# TeslaBMS_Shield_2.net
KiCad netlist of a schematic drawn in EAGLE
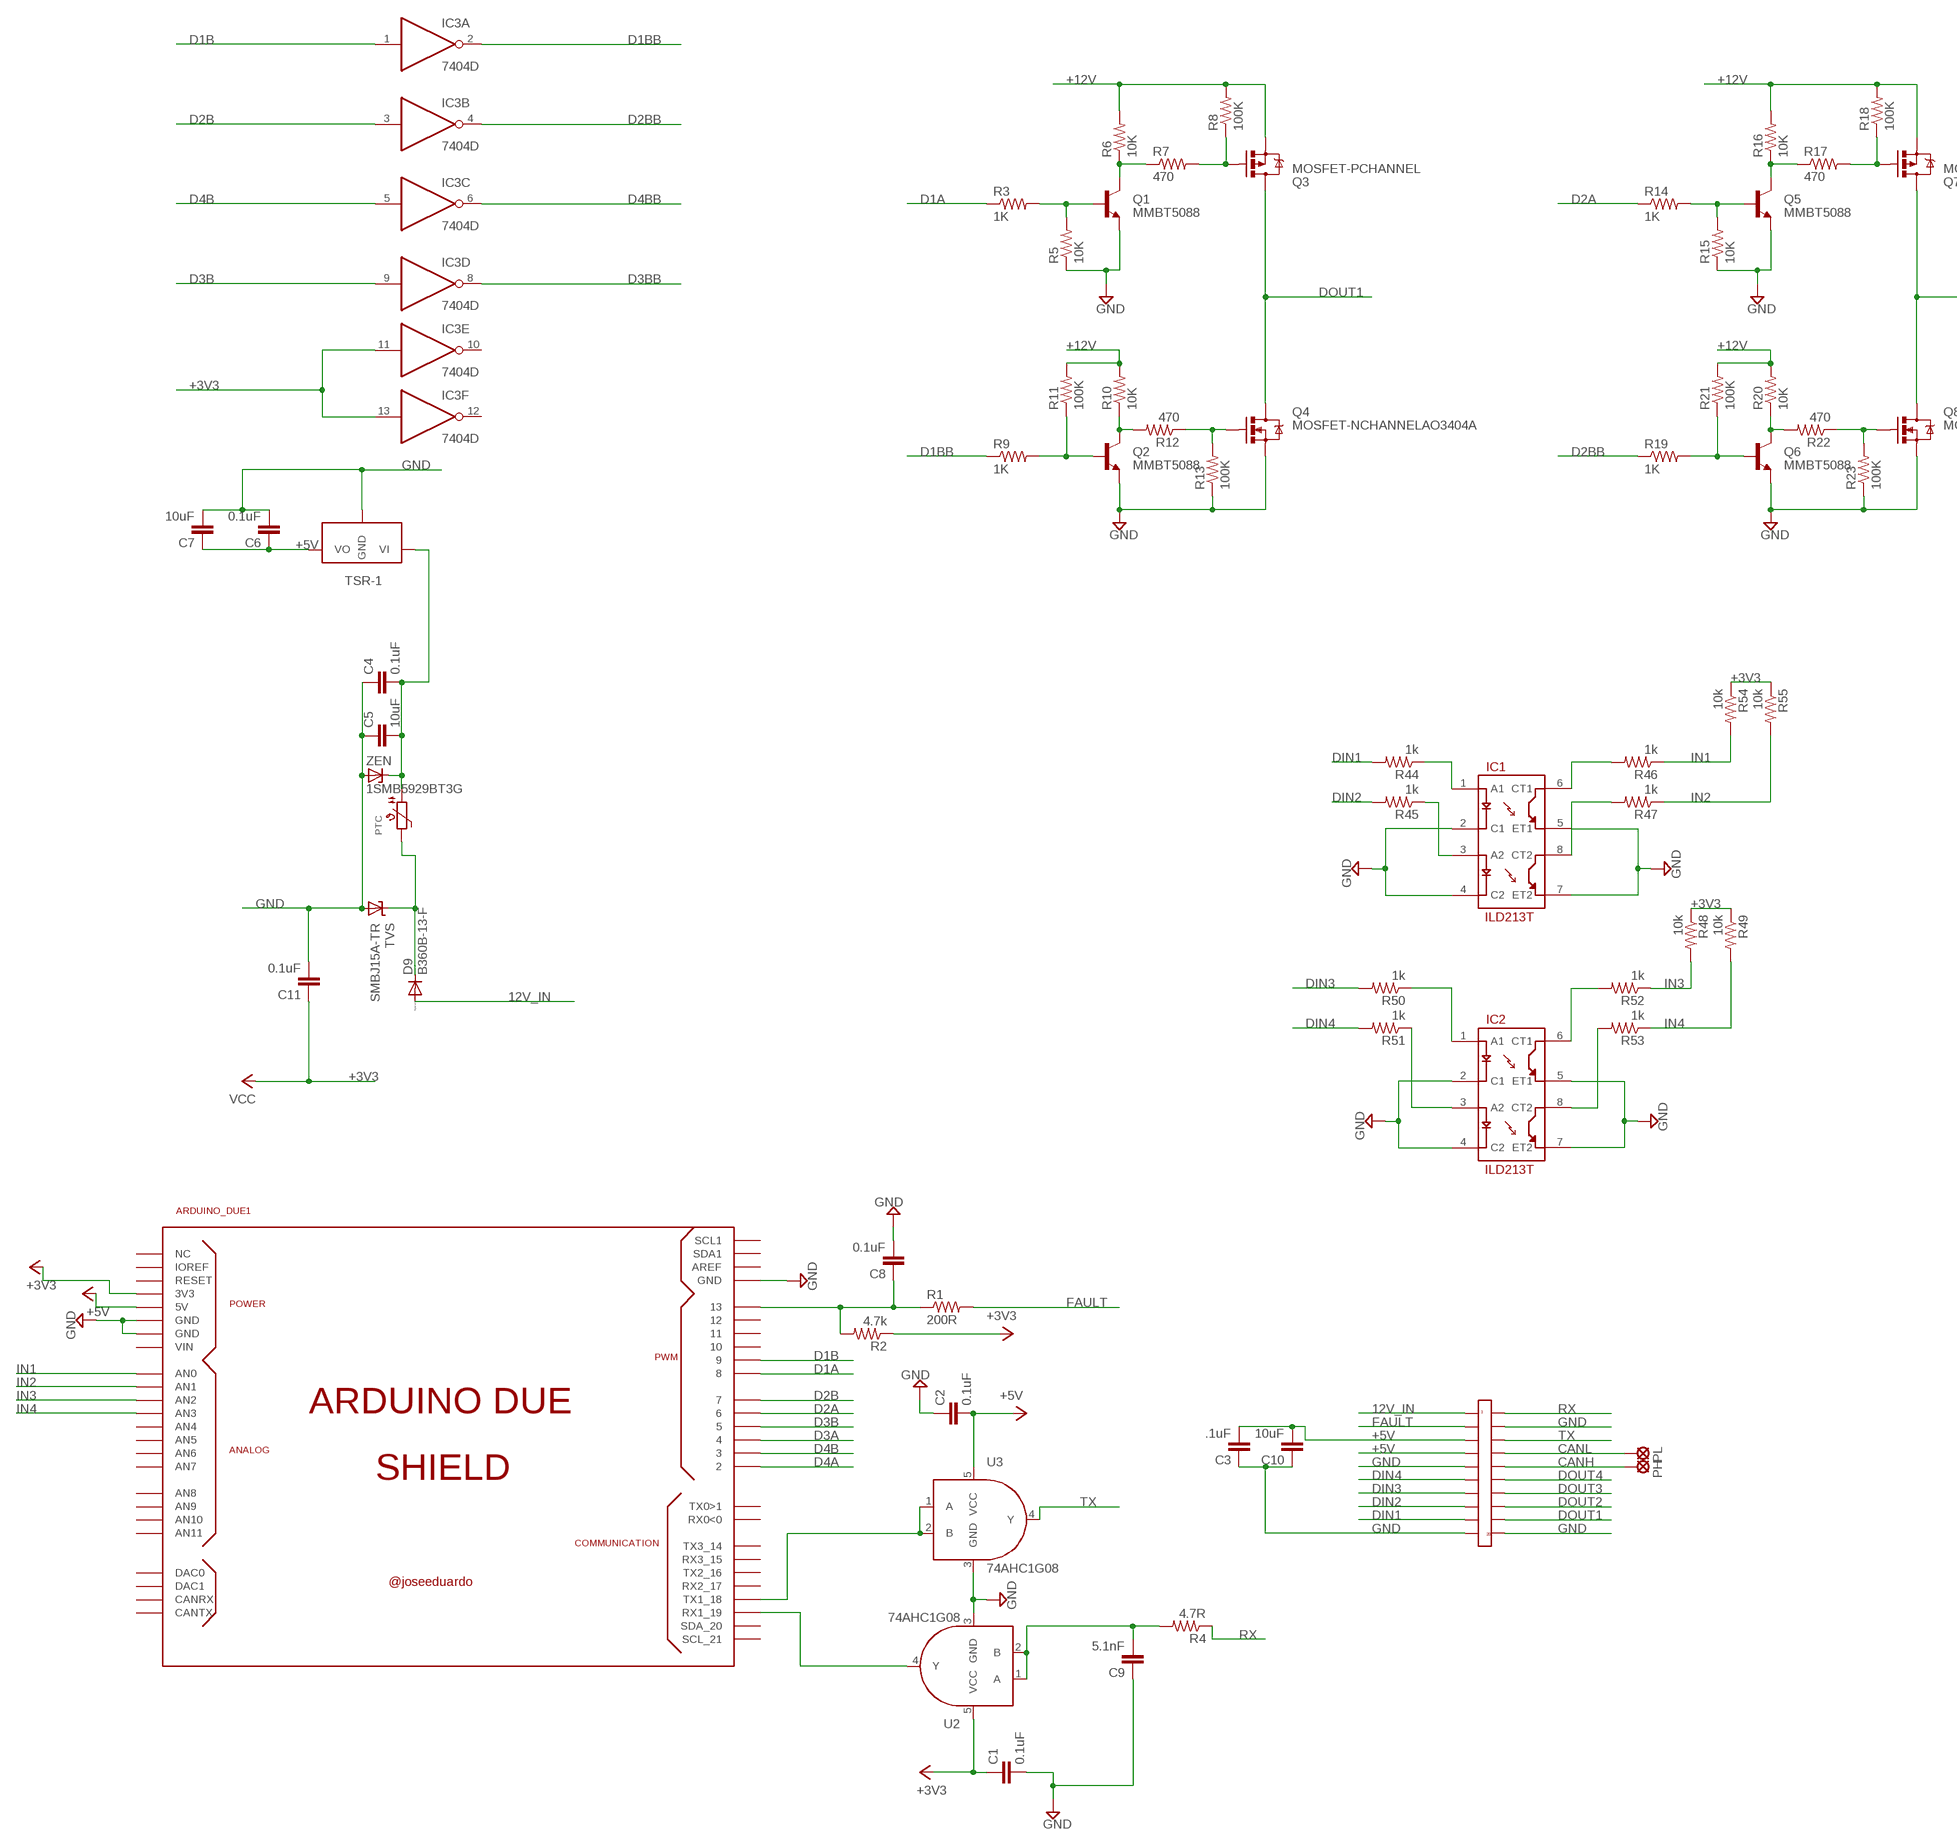
[diagram p0: schematic, sheet 1, part 1 of 2]
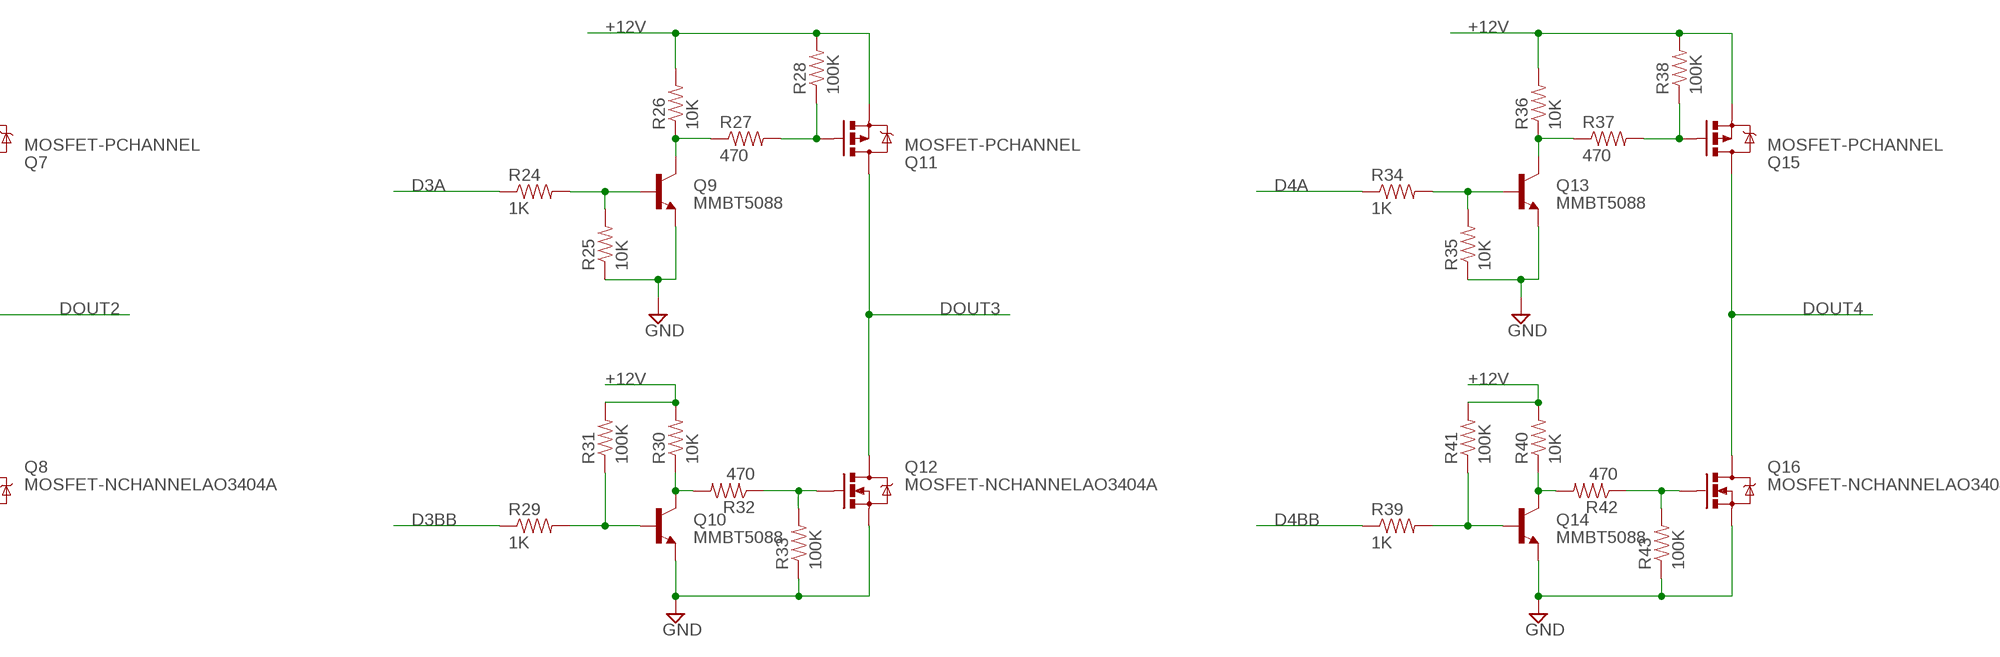
[diagram p1: schematic, sheet 1, part 2 of 2]

(export (version "E")
  (design (tool "Eeschema 10.0.6"))
  (components
    (comp (ref "ARDUINO_DUE1")
      (value "ARDUINO_DUE_SHIELD")
      (footprint "eagle-import:ARDUINO_DUE_SHIELD")
      (libsource (lib "eagle-import") (part "ARDUINO_DUE_SHIELD"))
    )
    (comp (ref "C1")
      (value "0.1uF")
      (footprint "eagle-import:0603-CAP")
      (libsource (lib "eagle-import") (part "CAP0603-CAP"))
    )
    (comp (ref "C2")
      (value "0.1uF")
      (footprint "eagle-import:0603-CAP")
      (libsource (lib "eagle-import") (part "CAP0603-CAP"))
    )
    (comp (ref "C3")
      (value ".1uF")
      (footprint "eagle-import:0603-CAP")
      (libsource (lib "eagle-import") (part "CAP0603-CAP"))
    )
    (comp (ref "C4")
      (value "0.1uF")
      (footprint "eagle-import:0805")
      (libsource (lib "eagle-import") (part "CAP0805"))
    )
    (comp (ref "C5")
      (value "10uF")
      (footprint "eagle-import:0805")
      (libsource (lib "eagle-import") (part "CAP0805"))
    )
    (comp (ref "C6")
      (value "0.1uF")
      (footprint "eagle-import:0805")
      (libsource (lib "eagle-import") (part "CAP0805"))
    )
    (comp (ref "C7")
      (value "10uF")
      (footprint "eagle-import:0805")
      (libsource (lib "eagle-import") (part "CAP0805"))
    )
    (comp (ref "C8")
      (value "0.1uF")
      (footprint "eagle-import:0603-CAP")
      (libsource (lib "eagle-import") (part "CAP0603-CAP"))
    )
    (comp (ref "C9")
      (value "5.1nF")
      (footprint "eagle-import:0603-CAP")
      (libsource (lib "eagle-import") (part "CAP0603-CAP"))
    )
    (comp (ref "C10")
      (value "10uF")
      (footprint "eagle-import:0603-CAP")
      (libsource (lib "eagle-import") (part "CAP0603-CAP"))
    )
    (comp (ref "C11")
      (value "0.1uF")
      (footprint "eagle-import:0805")
      (libsource (lib "eagle-import") (part "CAP0805"))
    )
    (comp (ref "D9")
      (value "B360B-13-F")
      (footprint "eagle-import:SMB")
      (libsource (lib "eagle-import") (part "DIODE-SMB"))
    )
    (comp (ref "IC1")
      (value "ILD213T")
      (footprint "eagle-import:SO08")
      (libsource (lib "eagle-import") (part "ILD213T"))
    )
    (comp (ref "IC2")
      (value "ILD213T")
      (footprint "eagle-import:SO08")
      (libsource (lib "eagle-import") (part "ILD213T"))
    )
    (comp (ref "IC3")
      (value "7404D")
      (footprint "eagle-import:SO14")
      (libsource (lib "eagle-import") (part "7404D"))
    )
    (comp (ref "PH")
      (value "SE11")
      (footprint "eagle-import:SE11")
      (libsource (lib "eagle-import") (part "SE11"))
    )
    (comp (ref "PL")
      (value "SE11")
      (footprint "eagle-import:SE11")
      (libsource (lib "eagle-import") (part "SE11"))
    )
    (comp (ref "PTC")
      (value "PTC1812")
      (footprint "eagle-import:PTC1812")
      (libsource (lib "eagle-import") (part "PTC1812"))
    )
    (comp (ref "Q1")
      (value "MMBT5088")
      (footprint "eagle-import:SOT23-3")
      (libsource (lib "eagle-import") (part "TRANSISTOR_NPNMMBT5088"))
    )
    (comp (ref "Q2")
      (value "MMBT5088")
      (footprint "eagle-import:SOT23-3")
      (libsource (lib "eagle-import") (part "TRANSISTOR_NPNMMBT5088"))
    )
    (comp (ref "Q3")
      (value "MOSFET-PCHANNEL")
      (footprint "eagle-import:SOT23-3")
      (libsource (lib "eagle-import") (part "MOSFET-PCHANNEL"))
    )
    (comp (ref "Q4")
      (value "MOSFET-NCHANNELAO3404A")
      (footprint "eagle-import:SOT23-3")
      (libsource (lib "eagle-import") (part "MOSFET-NCHANNELAO3404A"))
    )
    (comp (ref "Q5")
      (value "MMBT5088")
      (footprint "eagle-import:SOT23-3")
      (libsource (lib "eagle-import") (part "TRANSISTOR_NPNMMBT5088"))
    )
    (comp (ref "Q6")
      (value "MMBT5088")
      (footprint "eagle-import:SOT23-3")
      (libsource (lib "eagle-import") (part "TRANSISTOR_NPNMMBT5088"))
    )
    (comp (ref "Q7")
      (value "MOSFET-PCHANNEL")
      (footprint "eagle-import:SOT23-3")
      (libsource (lib "eagle-import") (part "MOSFET-PCHANNEL"))
    )
    (comp (ref "Q8")
      (value "MOSFET-NCHANNELAO3404A")
      (footprint "eagle-import:SOT23-3")
      (libsource (lib "eagle-import") (part "MOSFET-NCHANNELAO3404A"))
    )
    (comp (ref "Q9")
      (value "MMBT5088")
      (footprint "eagle-import:SOT23-3")
      (libsource (lib "eagle-import") (part "TRANSISTOR_NPNMMBT5088"))
    )
    (comp (ref "Q10")
      (value "MMBT5088")
      (footprint "eagle-import:SOT23-3")
      (libsource (lib "eagle-import") (part "TRANSISTOR_NPNMMBT5088"))
    )
    (comp (ref "Q11")
      (value "MOSFET-PCHANNEL")
      (footprint "eagle-import:SOT23-3")
      (libsource (lib "eagle-import") (part "MOSFET-PCHANNEL"))
    )
    (comp (ref "Q12")
      (value "MOSFET-NCHANNELAO3404A")
      (footprint "eagle-import:SOT23-3")
      (libsource (lib "eagle-import") (part "MOSFET-NCHANNELAO3404A"))
    )
    (comp (ref "Q13")
      (value "MMBT5088")
      (footprint "eagle-import:SOT23-3")
      (libsource (lib "eagle-import") (part "TRANSISTOR_NPNMMBT5088"))
    )
    (comp (ref "Q14")
      (value "MMBT5088")
      (footprint "eagle-import:SOT23-3")
      (libsource (lib "eagle-import") (part "TRANSISTOR_NPNMMBT5088"))
    )
    (comp (ref "Q15")
      (value "MOSFET-PCHANNEL")
      (footprint "eagle-import:SOT23-3")
      (libsource (lib "eagle-import") (part "MOSFET-PCHANNEL"))
    )
    (comp (ref "Q16")
      (value "MOSFET-NCHANNELAO3404A")
      (footprint "eagle-import:SOT23-3")
      (libsource (lib "eagle-import") (part "MOSFET-NCHANNELAO3404A"))
    )
    (comp (ref "R1")
      (value "200R")
      (footprint "eagle-import:0603-RES")
      (libsource (lib "eagle-import") (part "RESISTOR0603-RES"))
    )
    (comp (ref "R2")
      (value "4.7k")
      (footprint "eagle-import:0603-RES")
      (libsource (lib "eagle-import") (part "RESISTOR0603-RES"))
    )
    (comp (ref "R3")
      (value "1K")
      (footprint "eagle-import:0402-RES")
      (libsource (lib "eagle-import") (part "RESISTOR0402"))
    )
    (comp (ref "R4")
      (value "4.7R")
      (footprint "eagle-import:0603-RES")
      (libsource (lib "eagle-import") (part "RESISTOR0603-RES"))
    )
    (comp (ref "R5")
      (value "10K")
      (footprint "eagle-import:0402-RES")
      (libsource (lib "eagle-import") (part "RESISTOR0402"))
    )
    (comp (ref "R6")
      (value "10K")
      (footprint "eagle-import:0402-RES")
      (libsource (lib "eagle-import") (part "RESISTOR0402"))
    )
    (comp (ref "R7")
      (value "470")
      (footprint "eagle-import:0402-RES")
      (libsource (lib "eagle-import") (part "RESISTOR0402"))
    )
    (comp (ref "R8")
      (value "100K")
      (footprint "eagle-import:0402-RES")
      (libsource (lib "eagle-import") (part "RESISTOR0402"))
    )
    (comp (ref "R9")
      (value "1K")
      (footprint "eagle-import:0402-RES")
      (libsource (lib "eagle-import") (part "RESISTOR0402"))
    )
    (comp (ref "R10")
      (value "10K")
      (footprint "eagle-import:0402-RES")
      (libsource (lib "eagle-import") (part "RESISTOR0402"))
    )
    (comp (ref "R11")
      (value "100K")
      (footprint "eagle-import:0402-RES")
      (libsource (lib "eagle-import") (part "RESISTOR0402"))
    )
    (comp (ref "R12")
      (value "470")
      (footprint "eagle-import:0402-RES")
      (libsource (lib "eagle-import") (part "RESISTOR0402"))
    )
    (comp (ref "R13")
      (value "100K")
      (footprint "eagle-import:0402-RES")
      (libsource (lib "eagle-import") (part "RESISTOR0402"))
    )
    (comp (ref "R14")
      (value "1K")
      (footprint "eagle-import:0402-RES")
      (libsource (lib "eagle-import") (part "RESISTOR0402"))
    )
    (comp (ref "R15")
      (value "10K")
      (footprint "eagle-import:0402-RES")
      (libsource (lib "eagle-import") (part "RESISTOR0402"))
    )
    (comp (ref "R16")
      (value "10K")
      (footprint "eagle-import:0402-RES")
      (libsource (lib "eagle-import") (part "RESISTOR0402"))
    )
    (comp (ref "R17")
      (value "470")
      (footprint "eagle-import:0402-RES")
      (libsource (lib "eagle-import") (part "RESISTOR0402"))
    )
    (comp (ref "R18")
      (value "100K")
      (footprint "eagle-import:0402-RES")
      (libsource (lib "eagle-import") (part "RESISTOR0402"))
    )
    (comp (ref "R19")
      (value "1K")
      (footprint "eagle-import:0402-RES")
      (libsource (lib "eagle-import") (part "RESISTOR0402"))
    )
    (comp (ref "R20")
      (value "10K")
      (footprint "eagle-import:0402-RES")
      (libsource (lib "eagle-import") (part "RESISTOR0402"))
    )
    (comp (ref "R21")
      (value "100K")
      (footprint "eagle-import:0402-RES")
      (libsource (lib "eagle-import") (part "RESISTOR0402"))
    )
    (comp (ref "R22")
      (value "470")
      (footprint "eagle-import:0402-RES")
      (libsource (lib "eagle-import") (part "RESISTOR0402"))
    )
    (comp (ref "R23")
      (value "100K")
      (footprint "eagle-import:0402-RES")
      (libsource (lib "eagle-import") (part "RESISTOR0402"))
    )
    (comp (ref "R24")
      (value "1K")
      (footprint "eagle-import:0402-RES")
      (libsource (lib "eagle-import") (part "RESISTOR0402"))
    )
    (comp (ref "R25")
      (value "10K")
      (footprint "eagle-import:0402-RES")
      (libsource (lib "eagle-import") (part "RESISTOR0402"))
    )
    (comp (ref "R26")
      (value "10K")
      (footprint "eagle-import:0402-RES")
      (libsource (lib "eagle-import") (part "RESISTOR0402"))
    )
    (comp (ref "R27")
      (value "470")
      (footprint "eagle-import:0402-RES")
      (libsource (lib "eagle-import") (part "RESISTOR0402"))
    )
    (comp (ref "R28")
      (value "100K")
      (footprint "eagle-import:0402-RES")
      (libsource (lib "eagle-import") (part "RESISTOR0402"))
    )
    (comp (ref "R29")
      (value "1K")
      (footprint "eagle-import:0402-RES")
      (libsource (lib "eagle-import") (part "RESISTOR0402"))
    )
    (comp (ref "R30")
      (value "10K")
      (footprint "eagle-import:0402-RES")
      (libsource (lib "eagle-import") (part "RESISTOR0402"))
    )
    (comp (ref "R31")
      (value "100K")
      (footprint "eagle-import:0402-RES")
      (libsource (lib "eagle-import") (part "RESISTOR0402"))
    )
    (comp (ref "R32")
      (value "470")
      (footprint "eagle-import:0402-RES")
      (libsource (lib "eagle-import") (part "RESISTOR0402"))
    )
    (comp (ref "R33")
      (value "100K")
      (footprint "eagle-import:0402-RES")
      (libsource (lib "eagle-import") (part "RESISTOR0402"))
    )
    (comp (ref "R34")
      (value "1K")
      (footprint "eagle-import:0402-RES")
      (libsource (lib "eagle-import") (part "RESISTOR0402"))
    )
    (comp (ref "R35")
      (value "10K")
      (footprint "eagle-import:0402-RES")
      (libsource (lib "eagle-import") (part "RESISTOR0402"))
    )
    (comp (ref "R36")
      (value "10K")
      (footprint "eagle-import:0402-RES")
      (libsource (lib "eagle-import") (part "RESISTOR0402"))
    )
    (comp (ref "R37")
      (value "470")
      (footprint "eagle-import:0402-RES")
      (libsource (lib "eagle-import") (part "RESISTOR0402"))
    )
    (comp (ref "R38")
      (value "100K")
      (footprint "eagle-import:0402-RES")
      (libsource (lib "eagle-import") (part "RESISTOR0402"))
    )
    (comp (ref "R39")
      (value "1K")
      (footprint "eagle-import:0402-RES")
      (libsource (lib "eagle-import") (part "RESISTOR0402"))
    )
    (comp (ref "R40")
      (value "10K")
      (footprint "eagle-import:0402-RES")
      (libsource (lib "eagle-import") (part "RESISTOR0402"))
    )
    (comp (ref "R41")
      (value "100K")
      (footprint "eagle-import:0402-RES")
      (libsource (lib "eagle-import") (part "RESISTOR0402"))
    )
    (comp (ref "R42")
      (value "470")
      (footprint "eagle-import:0402-RES")
      (libsource (lib "eagle-import") (part "RESISTOR0402"))
    )
    (comp (ref "R43")
      (value "100K")
      (footprint "eagle-import:0402-RES")
      (libsource (lib "eagle-import") (part "RESISTOR0402"))
    )
    (comp (ref "R44")
      (value "1k")
      (footprint "eagle-import:0603-RES")
      (libsource (lib "eagle-import") (part "RESISTOR0603-RES"))
    )
    (comp (ref "R45")
      (value "1k")
      (footprint "eagle-import:0603-RES")
      (libsource (lib "eagle-import") (part "RESISTOR0603-RES"))
    )
    (comp (ref "R46")
      (value "1k")
      (footprint "eagle-import:0603-RES")
      (libsource (lib "eagle-import") (part "RESISTOR0603-RES"))
    )
    (comp (ref "R47")
      (value "1k")
      (footprint "eagle-import:0603-RES")
      (libsource (lib "eagle-import") (part "RESISTOR0603-RES"))
    )
    (comp (ref "R48")
      (value "10k")
      (footprint "eagle-import:0603-RES")
      (libsource (lib "eagle-import") (part "RESISTOR0603-RES"))
    )
    (comp (ref "R49")
      (value "10k")
      (footprint "eagle-import:0603-RES")
      (libsource (lib "eagle-import") (part "RESISTOR0603-RES"))
    )
    (comp (ref "R50")
      (value "1k")
      (footprint "eagle-import:0603-RES")
      (libsource (lib "eagle-import") (part "RESISTOR0603-RES"))
    )
    (comp (ref "R51")
      (value "1k")
      (footprint "eagle-import:0603-RES")
      (libsource (lib "eagle-import") (part "RESISTOR0603-RES"))
    )
    (comp (ref "R52")
      (value "1k")
      (footprint "eagle-import:0603-RES")
      (libsource (lib "eagle-import") (part "RESISTOR0603-RES"))
    )
    (comp (ref "R53")
      (value "1k")
      (footprint "eagle-import:0603-RES")
      (libsource (lib "eagle-import") (part "RESISTOR0603-RES"))
    )
    (comp (ref "R54")
      (value "10k")
      (footprint "eagle-import:0603-RES")
      (libsource (lib "eagle-import") (part "RESISTOR0603-RES"))
    )
    (comp (ref "R55")
      (value "10k")
      (footprint "eagle-import:0603-RES")
      (libsource (lib "eagle-import") (part "RESISTOR0603-RES"))
    )
    (comp (ref "TVS")
      (value "SMBJ15A-TR")
      (footprint "eagle-import:SMBJ")
      (libsource (lib "eagle-import") (part "SUPPRESSOR-SMBJ"))
    )
    (comp (ref "U$2")
      (value "VAL-U-LOK-20PIN")
      (footprint "eagle-import:VALULOK-20")
      (libsource (lib "eagle-import") (part "VAL-U-LOK-20PIN"))
    )
    (comp (ref "U2")
      (value "74AHC1G08")
      (footprint "eagle-import:SOT353")
      (libsource (lib "eagle-import") (part "74AHC1G08"))
    )
    (comp (ref "U3")
      (value "74AHC1G08")
      (footprint "eagle-import:SOT353")
      (libsource (lib "eagle-import") (part "74AHC1G08"))
    )
    (comp (ref "U9")
      (value "TSR-1")
      (footprint "eagle-import:TSR-1")
      (libsource (lib "eagle-import") (part "TSR-1"))
    )
    (comp (ref "ZEN")
      (value "1SMB5929BT3G")
      (footprint "eagle-import:SMB")
      (libsource (lib "eagle-import") (part "ZENER-DIODESMB"))
    )
  )
  (nets
    (net (code "1") (name "+3V3") (class "Default")
      (node (ref "ARDUINO_DUE1") (pin "3V3") (pinfunction "3V3_3V3") (pintype "bidirectional"))
      (node (ref "C1") (pin "1") (pinfunction "1_1") (pintype "passive"))
      (node (ref "C11") (pin "1") (pinfunction "1_1") (pintype "passive"))
      (node (ref "IC3") (pin "11") (pinfunction "I_11") (pintype "input"))
      (node (ref "IC3") (pin "13") (pinfunction "I_13") (pintype "input"))
      (node (ref "R2") (pin "1") (pinfunction "1_1") (pintype "passive"))
      (node (ref "R48") (pin "1") (pinfunction "1_1") (pintype "passive"))
      (node (ref "R49") (pin "1") (pinfunction "1_1") (pintype "passive"))
      (node (ref "R54") (pin "1") (pinfunction "1_1") (pintype "passive"))
      (node (ref "R55") (pin "1") (pinfunction "1_1") (pintype "passive"))
      (node (ref "U2") (pin "5") (pinfunction "VCC_5") (pintype "bidirectional"))
    )
    (net (code "2") (name "+5V") (class "Default")
      (node (ref "ARDUINO_DUE1") (pin "5V0") (pinfunction "5V_5V0") (pintype "bidirectional"))
      (node (ref "C10") (pin "2") (pinfunction "2_2") (pintype "passive"))
      (node (ref "C2") (pin "2") (pinfunction "2_2") (pintype "passive"))
      (node (ref "C3") (pin "2") (pinfunction "2_2") (pintype "passive"))
      (node (ref "C6") (pin "1") (pinfunction "1_1") (pintype "passive"))
      (node (ref "C7") (pin "1") (pinfunction "1_1") (pintype "passive"))
      (node (ref "U$2") (pin "P$3") (pinfunction "P$3_P$3") (pintype "bidirectional"))
      (node (ref "U$2") (pin "P$4") (pinfunction "P$4_P$4") (pintype "bidirectional"))
      (node (ref "U3") (pin "5") (pinfunction "VCC_5") (pintype "bidirectional"))
      (node (ref "U9") (pin "P$3") (pinfunction "VO_P$3") (pintype "bidirectional"))
    )
    (net (code "3") (name "/+12V") (class "Default")
      (node (ref "C4") (pin "2") (pinfunction "2_2") (pintype "passive"))
      (node (ref "C5") (pin "2") (pinfunction "2_2") (pintype "passive"))
      (node (ref "PTC") (pin "P$1") (pinfunction "1_P$1") (pintype "passive"))
      (node (ref "Q11") (pin "2") (pinfunction "S_2") (pintype "passive"))
      (node (ref "Q15") (pin "2") (pinfunction "S_2") (pintype "passive"))
      (node (ref "Q3") (pin "2") (pinfunction "S_2") (pintype "passive"))
      (node (ref "Q7") (pin "2") (pinfunction "S_2") (pintype "passive"))
      (node (ref "R10") (pin "2") (pinfunction "2_2") (pintype "passive"))
      (node (ref "R11") (pin "2") (pinfunction "2_2") (pintype "passive"))
      (node (ref "R16") (pin "2") (pinfunction "2_2") (pintype "passive"))
      (node (ref "R18") (pin "2") (pinfunction "2_2") (pintype "passive"))
      (node (ref "R20") (pin "2") (pinfunction "2_2") (pintype "passive"))
      (node (ref "R21") (pin "2") (pinfunction "2_2") (pintype "passive"))
      (node (ref "R26") (pin "2") (pinfunction "2_2") (pintype "passive"))
      (node (ref "R28") (pin "2") (pinfunction "2_2") (pintype "passive"))
      (node (ref "R30") (pin "2") (pinfunction "2_2") (pintype "passive"))
      (node (ref "R31") (pin "2") (pinfunction "2_2") (pintype "passive"))
      (node (ref "R36") (pin "2") (pinfunction "2_2") (pintype "passive"))
      (node (ref "R38") (pin "2") (pinfunction "2_2") (pintype "passive"))
      (node (ref "R40") (pin "2") (pinfunction "2_2") (pintype "passive"))
      (node (ref "R41") (pin "2") (pinfunction "2_2") (pintype "passive"))
      (node (ref "R6") (pin "2") (pinfunction "2_2") (pintype "passive"))
      (node (ref "R8") (pin "2") (pinfunction "2_2") (pintype "passive"))
      (node (ref "U9") (pin "P$1") (pinfunction "VI_P$1") (pintype "bidirectional"))
      (node (ref "ZEN") (pin "C") (pinfunction "C_C") (pintype "passive"))
    )
    (net (code "4") (name "/12V_IN") (class "Default")
      (node (ref "D9") (pin "A") (pinfunction "A_A") (pintype "passive"))
      (node (ref "U$2") (pin "P$1") (pinfunction "P$1_P$1") (pintype "bidirectional"))
    )
    (net (code "5") (name "/CANH") (class "Default")
      (node (ref "PH") (pin "MP") (pinfunction "MP_MP") (pintype "passive"))
      (node (ref "U$2") (pin "P$15") (pinfunction "P$15_P$15") (pintype "bidirectional"))
    )
    (net (code "6") (name "/CANL") (class "Default")
      (node (ref "PL") (pin "MP") (pinfunction "MP_MP") (pintype "passive"))
      (node (ref "U$2") (pin "P$14") (pinfunction "P$14_P$14") (pintype "bidirectional"))
    )
    (net (code "7") (name "/D1A") (class "Default")
      (node (ref "ARDUINO_DUE1") (pin "8") (pinfunction "8_8") (pintype "bidirectional"))
      (node (ref "R3") (pin "1") (pinfunction "1_1") (pintype "passive"))
    )
    (net (code "8") (name "/D1B") (class "Default")
      (node (ref "ARDUINO_DUE1") (pin "9") (pinfunction "9_9") (pintype "bidirectional"))
      (node (ref "IC3") (pin "1") (pinfunction "I_1") (pintype "input"))
    )
    (net (code "9") (name "/D1BB") (class "Default")
      (node (ref "IC3") (pin "2") (pinfunction "O_2") (pintype "output"))
      (node (ref "R9") (pin "1") (pinfunction "1_1") (pintype "passive"))
    )
    (net (code "10") (name "/D2A") (class "Default")
      (node (ref "ARDUINO_DUE1") (pin "6") (pinfunction "6_6") (pintype "bidirectional"))
      (node (ref "R14") (pin "1") (pinfunction "1_1") (pintype "passive"))
    )
    (net (code "11") (name "/D2B") (class "Default")
      (node (ref "ARDUINO_DUE1") (pin "7") (pinfunction "7_7") (pintype "bidirectional"))
      (node (ref "IC3") (pin "3") (pinfunction "I_3") (pintype "input"))
    )
    (net (code "12") (name "/D2BB") (class "Default")
      (node (ref "IC3") (pin "4") (pinfunction "O_4") (pintype "output"))
      (node (ref "R19") (pin "1") (pinfunction "1_1") (pintype "passive"))
    )
    (net (code "13") (name "/D3A") (class "Default")
      (node (ref "ARDUINO_DUE1") (pin "4") (pinfunction "4_4") (pintype "bidirectional"))
      (node (ref "R24") (pin "1") (pinfunction "1_1") (pintype "passive"))
    )
    (net (code "14") (name "/D3B") (class "Default")
      (node (ref "ARDUINO_DUE1") (pin "5") (pinfunction "5_5") (pintype "bidirectional"))
      (node (ref "IC3") (pin "9") (pinfunction "I_9") (pintype "input"))
    )
    (net (code "15") (name "/D3BB") (class "Default")
      (node (ref "IC3") (pin "8") (pinfunction "O_8") (pintype "output"))
      (node (ref "R29") (pin "1") (pinfunction "1_1") (pintype "passive"))
    )
    (net (code "16") (name "/D4A") (class "Default")
      (node (ref "ARDUINO_DUE1") (pin "2") (pinfunction "2_2") (pintype "bidirectional"))
      (node (ref "R34") (pin "1") (pinfunction "1_1") (pintype "passive"))
    )
    (net (code "17") (name "/D4B") (class "Default")
      (node (ref "ARDUINO_DUE1") (pin "3") (pinfunction "3_3") (pintype "bidirectional"))
      (node (ref "IC3") (pin "5") (pinfunction "I_5") (pintype "input"))
    )
    (net (code "18") (name "/D4BB") (class "Default")
      (node (ref "IC3") (pin "6") (pinfunction "O_6") (pintype "output"))
      (node (ref "R39") (pin "1") (pinfunction "1_1") (pintype "passive"))
    )
    (net (code "19") (name "/DIN1") (class "Default")
      (node (ref "R44") (pin "2") (pinfunction "2_2") (pintype "passive"))
      (node (ref "U$2") (pin "P$9") (pinfunction "P$9_P$9") (pintype "bidirectional"))
    )
    (net (code "20") (name "/DIN2") (class "Default")
      (node (ref "R45") (pin "2") (pinfunction "2_2") (pintype "passive"))
      (node (ref "U$2") (pin "P$8") (pinfunction "P$8_P$8") (pintype "bidirectional"))
    )
    (net (code "21") (name "/DIN3") (class "Default")
      (node (ref "R50") (pin "2") (pinfunction "2_2") (pintype "passive"))
      (node (ref "U$2") (pin "P$7") (pinfunction "P$7_P$7") (pintype "bidirectional"))
    )
    (net (code "22") (name "/DIN4") (class "Default")
      (node (ref "R51") (pin "2") (pinfunction "2_2") (pintype "passive"))
      (node (ref "U$2") (pin "P$6") (pinfunction "P$6_P$6") (pintype "bidirectional"))
    )
    (net (code "23") (name "/DOUT1") (class "Default")
      (node (ref "Q3") (pin "3") (pinfunction "D_3") (pintype "passive"))
      (node (ref "Q4") (pin "3") (pinfunction "D_3") (pintype "passive"))
      (node (ref "U$2") (pin "P$19") (pinfunction "P$19_P$19") (pintype "bidirectional"))
    )
    (net (code "24") (name "/DOUT2") (class "Default")
      (node (ref "Q7") (pin "3") (pinfunction "D_3") (pintype "passive"))
      (node (ref "Q8") (pin "3") (pinfunction "D_3") (pintype "passive"))
      (node (ref "U$2") (pin "P$18") (pinfunction "P$18_P$18") (pintype "bidirectional"))
    )
    (net (code "25") (name "/DOUT3") (class "Default")
      (node (ref "Q11") (pin "3") (pinfunction "D_3") (pintype "passive"))
      (node (ref "Q12") (pin "3") (pinfunction "D_3") (pintype "passive"))
      (node (ref "U$2") (pin "P$17") (pinfunction "P$17_P$17") (pintype "bidirectional"))
    )
    (net (code "26") (name "/DOUT4") (class "Default")
      (node (ref "Q15") (pin "3") (pinfunction "D_3") (pintype "passive"))
      (node (ref "Q16") (pin "3") (pinfunction "D_3") (pintype "passive"))
      (node (ref "U$2") (pin "P$16") (pinfunction "P$16_P$16") (pintype "bidirectional"))
    )
    (net (code "27") (name "/FAULT") (class "Default")
      (node (ref "R1") (pin "2") (pinfunction "2_2") (pintype "passive"))
      (node (ref "U$2") (pin "P$2") (pinfunction "P$2_P$2") (pintype "bidirectional"))
    )
    (net (code "28") (name "/IN1") (class "Default")
      (node (ref "ARDUINO_DUE1") (pin "A0") (pinfunction "AN0_A0") (pintype "bidirectional"))
      (node (ref "R46") (pin "1") (pinfunction "1_1") (pintype "passive"))
      (node (ref "R54") (pin "2") (pinfunction "2_2") (pintype "passive"))
    )
    (net (code "29") (name "/IN2") (class "Default")
      (node (ref "ARDUINO_DUE1") (pin "A1") (pinfunction "AN1_A1") (pintype "bidirectional"))
      (node (ref "R47") (pin "1") (pinfunction "1_1") (pintype "passive"))
      (node (ref "R55") (pin "2") (pinfunction "2_2") (pintype "passive"))
    )
    (net (code "30") (name "/IN3") (class "Default")
      (node (ref "ARDUINO_DUE1") (pin "A2") (pinfunction "AN2_A2") (pintype "bidirectional"))
      (node (ref "R48") (pin "2") (pinfunction "2_2") (pintype "passive"))
      (node (ref "R52") (pin "1") (pinfunction "1_1") (pintype "passive"))
    )
    (net (code "31") (name "/IN4") (class "Default")
      (node (ref "ARDUINO_DUE1") (pin "A3") (pinfunction "AN3_A3") (pintype "bidirectional"))
      (node (ref "R49") (pin "2") (pinfunction "2_2") (pintype "passive"))
      (node (ref "R53") (pin "1") (pinfunction "1_1") (pintype "passive"))
    )
    (net (code "32") (name "/RX") (class "Default")
      (node (ref "R4") (pin "1") (pinfunction "1_1") (pintype "passive"))
      (node (ref "U$2") (pin "P$11") (pinfunction "P$11_P$11") (pintype "bidirectional"))
    )
    (net (code "33") (name "/TX") (class "Default")
      (node (ref "U$2") (pin "P$13") (pinfunction "P$13_P$13") (pintype "bidirectional"))
      (node (ref "U3") (pin "4") (pinfunction "Y_4") (pintype "bidirectional"))
    )
    (net (code "34") (name "GND") (class "Default")
      (node (ref "ARDUINO_DUE1") (pin "GND") (pinfunction "GND_GND") (pintype "bidirectional"))
      (node (ref "ARDUINO_DUE1") (pin "GND_1") (pinfunction "GND_GND_1") (pintype "bidirectional"))
      (node (ref "ARDUINO_DUE1") (pin "GND_4") (pinfunction "GND_GND_4") (pintype "bidirectional"))
      (node (ref "C1") (pin "2") (pinfunction "2_2") (pintype "passive"))
      (node (ref "C10") (pin "1") (pinfunction "1_1") (pintype "passive"))
      (node (ref "C11") (pin "2") (pinfunction "2_2") (pintype "passive"))
      (node (ref "C2") (pin "1") (pinfunction "1_1") (pintype "passive"))
      (node (ref "C3") (pin "1") (pinfunction "1_1") (pintype "passive"))
      (node (ref "C4") (pin "1") (pinfunction "1_1") (pintype "passive"))
      (node (ref "C5") (pin "1") (pinfunction "1_1") (pintype "passive"))
      (node (ref "C6") (pin "2") (pinfunction "2_2") (pintype "passive"))
      (node (ref "C7") (pin "2") (pinfunction "2_2") (pintype "passive"))
      (node (ref "C8") (pin "2") (pinfunction "2_2") (pintype "passive"))
      (node (ref "C9") (pin "1") (pinfunction "1_1") (pintype "passive"))
      (node (ref "IC1") (pin "2") (pinfunction "C1_2") (pintype "bidirectional"))
      (node (ref "IC1") (pin "4") (pinfunction "C2_4") (pintype "bidirectional"))
      (node (ref "IC1") (pin "5") (pinfunction "ET1_5") (pintype "bidirectional"))
      (node (ref "IC1") (pin "7") (pinfunction "ET2_7") (pintype "bidirectional"))
      (node (ref "IC2") (pin "2") (pinfunction "C1_2") (pintype "bidirectional"))
      (node (ref "IC2") (pin "4") (pinfunction "C2_4") (pintype "bidirectional"))
      (node (ref "IC2") (pin "5") (pinfunction "ET1_5") (pintype "bidirectional"))
      (node (ref "IC2") (pin "7") (pinfunction "ET2_7") (pintype "bidirectional"))
      (node (ref "Q1") (pin "2") (pinfunction "E_2") (pintype "passive"))
      (node (ref "Q10") (pin "2") (pinfunction "E_2") (pintype "passive"))
      (node (ref "Q12") (pin "2") (pinfunction "S_2") (pintype "passive"))
      (node (ref "Q13") (pin "2") (pinfunction "E_2") (pintype "passive"))
      (node (ref "Q14") (pin "2") (pinfunction "E_2") (pintype "passive"))
      (node (ref "Q16") (pin "2") (pinfunction "S_2") (pintype "passive"))
      (node (ref "Q2") (pin "2") (pinfunction "E_2") (pintype "passive"))
      (node (ref "Q4") (pin "2") (pinfunction "S_2") (pintype "passive"))
      (node (ref "Q5") (pin "2") (pinfunction "E_2") (pintype "passive"))
      (node (ref "Q6") (pin "2") (pinfunction "E_2") (pintype "passive"))
      (node (ref "Q8") (pin "2") (pinfunction "S_2") (pintype "passive"))
      (node (ref "Q9") (pin "2") (pinfunction "E_2") (pintype "passive"))
      (node (ref "R13") (pin "1") (pinfunction "1_1") (pintype "passive"))
      (node (ref "R15") (pin "1") (pinfunction "1_1") (pintype "passive"))
      (node (ref "R23") (pin "1") (pinfunction "1_1") (pintype "passive"))
      (node (ref "R25") (pin "1") (pinfunction "1_1") (pintype "passive"))
      (node (ref "R33") (pin "1") (pinfunction "1_1") (pintype "passive"))
      (node (ref "R35") (pin "1") (pinfunction "1_1") (pintype "passive"))
      (node (ref "R43") (pin "1") (pinfunction "1_1") (pintype "passive"))
      (node (ref "R5") (pin "1") (pinfunction "1_1") (pintype "passive"))
      (node (ref "TVS") (pin "A") (pinfunction "A_A") (pintype "passive"))
      (node (ref "U$2") (pin "P$10") (pinfunction "P$10_P$10") (pintype "bidirectional"))
      (node (ref "U$2") (pin "P$12") (pinfunction "P$12_P$12") (pintype "bidirectional"))
      (node (ref "U$2") (pin "P$20") (pinfunction "P$20_P$20") (pintype "bidirectional"))
      (node (ref "U$2") (pin "P$5") (pinfunction "P$5_P$5") (pintype "bidirectional"))
      (node (ref "U2") (pin "3") (pinfunction "GND_3") (pintype "bidirectional"))
      (node (ref "U3") (pin "3") (pinfunction "GND_3") (pintype "bidirectional"))
      (node (ref "U9") (pin "P$2") (pinfunction "GND_P$2") (pintype "bidirectional"))
      (node (ref "ZEN") (pin "A") (pinfunction "A_A") (pintype "passive"))
    )
    (net (code "35") (name "Net-(ARDUINO_DUE1-Pad13)") (class "Default")
      (node (ref "ARDUINO_DUE1") (pin "13") (pinfunction "13_13") (pintype "bidirectional"))
      (node (ref "C8") (pin "1") (pinfunction "1_1") (pintype "passive"))
      (node (ref "R1") (pin "1") (pinfunction "1_1") (pintype "passive"))
      (node (ref "R2") (pin "2") (pinfunction "2_2") (pintype "passive"))
    )
    (net (code "36") (name "Net-(ARDUINO_DUE1-RX1_19)") (class "Default")
      (node (ref "ARDUINO_DUE1") (pin "19") (pinfunction "RX1_19_19") (pintype "bidirectional"))
      (node (ref "U2") (pin "4") (pinfunction "Y_4") (pintype "bidirectional"))
    )
    (net (code "37") (name "Net-(ARDUINO_DUE1-TX1_18)") (class "Default")
      (node (ref "ARDUINO_DUE1") (pin "18") (pinfunction "TX1_18_18") (pintype "bidirectional"))
      (node (ref "U3") (pin "1") (pinfunction "A_1") (pintype "bidirectional"))
      (node (ref "U3") (pin "2") (pinfunction "B_2") (pintype "bidirectional"))
    )
    (net (code "38") (name "Net-(IC1-A1)") (class "Default")
      (node (ref "IC1") (pin "1") (pinfunction "A1_1") (pintype "bidirectional"))
      (node (ref "R44") (pin "1") (pinfunction "1_1") (pintype "passive"))
    )
    (net (code "39") (name "Net-(IC1-A2)") (class "Default")
      (node (ref "IC1") (pin "3") (pinfunction "A2_3") (pintype "bidirectional"))
      (node (ref "R45") (pin "1") (pinfunction "1_1") (pintype "passive"))
    )
    (net (code "40") (name "Net-(IC1-CT1)") (class "Default")
      (node (ref "IC1") (pin "6") (pinfunction "CT1_6") (pintype "bidirectional"))
      (node (ref "R46") (pin "2") (pinfunction "2_2") (pintype "passive"))
    )
    (net (code "41") (name "Net-(IC1-CT2)") (class "Default")
      (node (ref "IC1") (pin "8") (pinfunction "CT2_8") (pintype "bidirectional"))
      (node (ref "R47") (pin "2") (pinfunction "2_2") (pintype "passive"))
    )
    (net (code "42") (name "Net-(IC2-A1)") (class "Default")
      (node (ref "IC2") (pin "1") (pinfunction "A1_1") (pintype "bidirectional"))
      (node (ref "R50") (pin "1") (pinfunction "1_1") (pintype "passive"))
    )
    (net (code "43") (name "Net-(IC2-A2)") (class "Default")
      (node (ref "IC2") (pin "3") (pinfunction "A2_3") (pintype "bidirectional"))
      (node (ref "R51") (pin "1") (pinfunction "1_1") (pintype "passive"))
    )
    (net (code "44") (name "Net-(IC2-CT1)") (class "Default")
      (node (ref "IC2") (pin "6") (pinfunction "CT1_6") (pintype "bidirectional"))
      (node (ref "R52") (pin "2") (pinfunction "2_2") (pintype "passive"))
    )
    (net (code "45") (name "Net-(IC2-CT2)") (class "Default")
      (node (ref "IC2") (pin "8") (pinfunction "CT2_8") (pintype "bidirectional"))
      (node (ref "R53") (pin "2") (pinfunction "2_2") (pintype "passive"))
    )
    (net (code "46") (name "Net-(PTC-2)") (class "Default")
      (node (ref "D9") (pin "C") (pinfunction "C_C") (pintype "passive"))
      (node (ref "PTC") (pin "P$2") (pinfunction "2_P$2") (pintype "passive"))
      (node (ref "TVS") (pin "C") (pinfunction "C_C") (pintype "passive"))
    )
    (net (code "47") (name "Net-(Q1-B)") (class "Default")
      (node (ref "Q1") (pin "1") (pinfunction "B_1") (pintype "passive"))
      (node (ref "R3") (pin "2") (pinfunction "2_2") (pintype "passive"))
      (node (ref "R5") (pin "2") (pinfunction "2_2") (pintype "passive"))
    )
    (net (code "48") (name "Net-(Q1-C)") (class "Default")
      (node (ref "Q1") (pin "3") (pinfunction "C_3") (pintype "passive"))
      (node (ref "R6") (pin "1") (pinfunction "1_1") (pintype "passive"))
      (node (ref "R7") (pin "1") (pinfunction "1_1") (pintype "passive"))
    )
    (net (code "49") (name "Net-(Q2-B)") (class "Default")
      (node (ref "Q2") (pin "1") (pinfunction "B_1") (pintype "passive"))
      (node (ref "R11") (pin "1") (pinfunction "1_1") (pintype "passive"))
      (node (ref "R9") (pin "2") (pinfunction "2_2") (pintype "passive"))
    )
    (net (code "50") (name "Net-(Q2-C)") (class "Default")
      (node (ref "Q2") (pin "3") (pinfunction "C_3") (pintype "passive"))
      (node (ref "R10") (pin "1") (pinfunction "1_1") (pintype "passive"))
      (node (ref "R12") (pin "2") (pinfunction "2_2") (pintype "passive"))
    )
    (net (code "51") (name "Net-(Q3-G)") (class "Default")
      (node (ref "Q3") (pin "1") (pinfunction "G_1") (pintype "passive"))
      (node (ref "R7") (pin "2") (pinfunction "2_2") (pintype "passive"))
      (node (ref "R8") (pin "1") (pinfunction "1_1") (pintype "passive"))
    )
    (net (code "52") (name "Net-(Q4-G)") (class "Default")
      (node (ref "Q4") (pin "1") (pinfunction "G_1") (pintype "passive"))
      (node (ref "R12") (pin "1") (pinfunction "1_1") (pintype "passive"))
      (node (ref "R13") (pin "2") (pinfunction "2_2") (pintype "passive"))
    )
    (net (code "53") (name "Net-(Q5-B)") (class "Default")
      (node (ref "Q5") (pin "1") (pinfunction "B_1") (pintype "passive"))
      (node (ref "R14") (pin "2") (pinfunction "2_2") (pintype "passive"))
      (node (ref "R15") (pin "2") (pinfunction "2_2") (pintype "passive"))
    )
    (net (code "54") (name "Net-(Q5-C)") (class "Default")
      (node (ref "Q5") (pin "3") (pinfunction "C_3") (pintype "passive"))
      (node (ref "R16") (pin "1") (pinfunction "1_1") (pintype "passive"))
      (node (ref "R17") (pin "1") (pinfunction "1_1") (pintype "passive"))
    )
    (net (code "55") (name "Net-(Q6-B)") (class "Default")
      (node (ref "Q6") (pin "1") (pinfunction "B_1") (pintype "passive"))
      (node (ref "R19") (pin "2") (pinfunction "2_2") (pintype "passive"))
      (node (ref "R21") (pin "1") (pinfunction "1_1") (pintype "passive"))
    )
    (net (code "56") (name "Net-(Q6-C)") (class "Default")
      (node (ref "Q6") (pin "3") (pinfunction "C_3") (pintype "passive"))
      (node (ref "R20") (pin "1") (pinfunction "1_1") (pintype "passive"))
      (node (ref "R22") (pin "2") (pinfunction "2_2") (pintype "passive"))
    )
    (net (code "57") (name "Net-(Q7-G)") (class "Default")
      (node (ref "Q7") (pin "1") (pinfunction "G_1") (pintype "passive"))
      (node (ref "R17") (pin "2") (pinfunction "2_2") (pintype "passive"))
      (node (ref "R18") (pin "1") (pinfunction "1_1") (pintype "passive"))
    )
    (net (code "58") (name "Net-(Q8-G)") (class "Default")
      (node (ref "Q8") (pin "1") (pinfunction "G_1") (pintype "passive"))
      (node (ref "R22") (pin "1") (pinfunction "1_1") (pintype "passive"))
      (node (ref "R23") (pin "2") (pinfunction "2_2") (pintype "passive"))
    )
    (net (code "59") (name "Net-(Q9-B)") (class "Default")
      (node (ref "Q9") (pin "1") (pinfunction "B_1") (pintype "passive"))
      (node (ref "R24") (pin "2") (pinfunction "2_2") (pintype "passive"))
      (node (ref "R25") (pin "2") (pinfunction "2_2") (pintype "passive"))
    )
    (net (code "60") (name "Net-(Q9-C)") (class "Default")
      (node (ref "Q9") (pin "3") (pinfunction "C_3") (pintype "passive"))
      (node (ref "R26") (pin "1") (pinfunction "1_1") (pintype "passive"))
      (node (ref "R27") (pin "1") (pinfunction "1_1") (pintype "passive"))
    )
    (net (code "61") (name "Net-(Q10-B)") (class "Default")
      (node (ref "Q10") (pin "1") (pinfunction "B_1") (pintype "passive"))
      (node (ref "R29") (pin "2") (pinfunction "2_2") (pintype "passive"))
      (node (ref "R31") (pin "1") (pinfunction "1_1") (pintype "passive"))
    )
    (net (code "62") (name "Net-(Q10-C)") (class "Default")
      (node (ref "Q10") (pin "3") (pinfunction "C_3") (pintype "passive"))
      (node (ref "R30") (pin "1") (pinfunction "1_1") (pintype "passive"))
      (node (ref "R32") (pin "2") (pinfunction "2_2") (pintype "passive"))
    )
    (net (code "63") (name "Net-(Q11-G)") (class "Default")
      (node (ref "Q11") (pin "1") (pinfunction "G_1") (pintype "passive"))
      (node (ref "R27") (pin "2") (pinfunction "2_2") (pintype "passive"))
      (node (ref "R28") (pin "1") (pinfunction "1_1") (pintype "passive"))
    )
    (net (code "64") (name "Net-(Q12-G)") (class "Default")
      (node (ref "Q12") (pin "1") (pinfunction "G_1") (pintype "passive"))
      (node (ref "R32") (pin "1") (pinfunction "1_1") (pintype "passive"))
      (node (ref "R33") (pin "2") (pinfunction "2_2") (pintype "passive"))
    )
    (net (code "65") (name "Net-(Q13-B)") (class "Default")
      (node (ref "Q13") (pin "1") (pinfunction "B_1") (pintype "passive"))
      (node (ref "R34") (pin "2") (pinfunction "2_2") (pintype "passive"))
      (node (ref "R35") (pin "2") (pinfunction "2_2") (pintype "passive"))
    )
    (net (code "66") (name "Net-(Q13-C)") (class "Default")
      (node (ref "Q13") (pin "3") (pinfunction "C_3") (pintype "passive"))
      (node (ref "R36") (pin "1") (pinfunction "1_1") (pintype "passive"))
      (node (ref "R37") (pin "1") (pinfunction "1_1") (pintype "passive"))
    )
    (net (code "67") (name "Net-(Q14-B)") (class "Default")
      (node (ref "Q14") (pin "1") (pinfunction "B_1") (pintype "passive"))
      (node (ref "R39") (pin "2") (pinfunction "2_2") (pintype "passive"))
      (node (ref "R41") (pin "1") (pinfunction "1_1") (pintype "passive"))
    )
    (net (code "68") (name "Net-(Q14-C)") (class "Default")
      (node (ref "Q14") (pin "3") (pinfunction "C_3") (pintype "passive"))
      (node (ref "R40") (pin "1") (pinfunction "1_1") (pintype "passive"))
      (node (ref "R42") (pin "2") (pinfunction "2_2") (pintype "passive"))
    )
    (net (code "69") (name "Net-(Q15-G)") (class "Default")
      (node (ref "Q15") (pin "1") (pinfunction "G_1") (pintype "passive"))
      (node (ref "R37") (pin "2") (pinfunction "2_2") (pintype "passive"))
      (node (ref "R38") (pin "1") (pinfunction "1_1") (pintype "passive"))
    )
    (net (code "70") (name "Net-(Q16-G)") (class "Default")
      (node (ref "Q16") (pin "1") (pinfunction "G_1") (pintype "passive"))
      (node (ref "R42") (pin "1") (pinfunction "1_1") (pintype "passive"))
      (node (ref "R43") (pin "2") (pinfunction "2_2") (pintype "passive"))
    )
    (net (code "71") (name "Net-(U2-A)") (class "Default")
      (node (ref "C9") (pin "2") (pinfunction "2_2") (pintype "passive"))
      (node (ref "R4") (pin "2") (pinfunction "2_2") (pintype "passive"))
      (node (ref "U2") (pin "1") (pinfunction "A_1") (pintype "bidirectional"))
      (node (ref "U2") (pin "2") (pinfunction "B_2") (pintype "bidirectional"))
    )
    (net (code "72") (name "unconnected-(ARDUINO_DUE1-AN4-PadA4)") (class "Default")
      (node (ref "ARDUINO_DUE1") (pin "A4") (pinfunction "AN4_A4") (pintype "bidirectional"))
    )
    (net (code "73") (name "unconnected-(ARDUINO_DUE1-AN5-PadA5)") (class "Default")
      (node (ref "ARDUINO_DUE1") (pin "A5") (pinfunction "AN5_A5") (pintype "bidirectional"))
    )
    (net (code "74") (name "unconnected-(ARDUINO_DUE1-AN6-PadA6)") (class "Default")
      (node (ref "ARDUINO_DUE1") (pin "A6") (pinfunction "AN6_A6") (pintype "bidirectional"))
    )
    (net (code "75") (name "unconnected-(ARDUINO_DUE1-AN7-PadA7)") (class "Default")
      (node (ref "ARDUINO_DUE1") (pin "A7") (pinfunction "AN7_A7") (pintype "bidirectional"))
    )
    (net (code "76") (name "unconnected-(ARDUINO_DUE1-AN8-PadA8)") (class "Default")
      (node (ref "ARDUINO_DUE1") (pin "A8") (pinfunction "AN8_A8") (pintype "bidirectional"))
    )
    (net (code "77") (name "unconnected-(ARDUINO_DUE1-AN9-PadA9)") (class "Default")
      (node (ref "ARDUINO_DUE1") (pin "A9") (pinfunction "AN9_A9") (pintype "bidirectional"))
    )
    (net (code "78") (name "unconnected-(ARDUINO_DUE1-AN10-PadA10)") (class "Default")
      (node (ref "ARDUINO_DUE1") (pin "A10") (pinfunction "AN10_A10") (pintype "bidirectional"))
    )
    (net (code "79") (name "unconnected-(ARDUINO_DUE1-AN11-PadA11)") (class "Default")
      (node (ref "ARDUINO_DUE1") (pin "A11") (pinfunction "AN11_A11") (pintype "bidirectional"))
    )
    (net (code "80") (name "unconnected-(ARDUINO_DUE1-NC-PadNC_2)") (class "Default")
      (node (ref "ARDUINO_DUE1") (pin "NC_2") (pinfunction "NC_NC_2") (pintype "no_connect"))
    )
    (net (code "81") (name "unconnected-(ARDUINO_DUE1-Pad10)") (class "Default")
      (node (ref "ARDUINO_DUE1") (pin "10") (pinfunction "10_10") (pintype "bidirectional"))
    )
    (net (code "82") (name "unconnected-(ARDUINO_DUE1-Pad11)") (class "Default")
      (node (ref "ARDUINO_DUE1") (pin "11") (pinfunction "11_11") (pintype "bidirectional"))
    )
    (net (code "83") (name "unconnected-(ARDUINO_DUE1-Pad12)") (class "Default")
      (node (ref "ARDUINO_DUE1") (pin "12") (pinfunction "12_12") (pintype "bidirectional"))
    )
    (net (code "84") (name "unconnected-(ARDUINO_DUE1-PadAREF)") (class "Default")
      (node (ref "ARDUINO_DUE1") (pin "AREF") (pinfunction "AREF_AREF") (pintype "bidirectional"))
    )
    (net (code "85") (name "unconnected-(ARDUINO_DUE1-PadCANRX)") (class "Default")
      (node (ref "ARDUINO_DUE1") (pin "CANRX") (pinfunction "CANRX_CANRX") (pintype "bidirectional"))
    )
    (net (code "86") (name "unconnected-(ARDUINO_DUE1-PadCANTX)") (class "Default")
      (node (ref "ARDUINO_DUE1") (pin "CANTX") (pinfunction "CANTX_CANTX") (pintype "bidirectional"))
    )
    (net (code "87") (name "unconnected-(ARDUINO_DUE1-PadDAC0)") (class "Default")
      (node (ref "ARDUINO_DUE1") (pin "DAC0") (pinfunction "DAC0_DAC0") (pintype "bidirectional"))
    )
    (net (code "88") (name "unconnected-(ARDUINO_DUE1-PadDAC1)") (class "Default")
      (node (ref "ARDUINO_DUE1") (pin "DAC1") (pinfunction "DAC1_DAC1") (pintype "bidirectional"))
    )
    (net (code "89") (name "unconnected-(ARDUINO_DUE1-PadIOREF)") (class "Default")
      (node (ref "ARDUINO_DUE1") (pin "IOREF") (pinfunction "IOREF_IOREF") (pintype "bidirectional"))
    )
    (net (code "90") (name "unconnected-(ARDUINO_DUE1-PadRESET)") (class "Default")
      (node (ref "ARDUINO_DUE1") (pin "RESET") (pinfunction "RESET_RESET") (pintype "bidirectional"))
    )
    (net (code "91") (name "unconnected-(ARDUINO_DUE1-PadSCL1)") (class "Default")
      (node (ref "ARDUINO_DUE1") (pin "SCL1") (pinfunction "SCL1_SCL1") (pintype "bidirectional"))
    )
    (net (code "92") (name "unconnected-(ARDUINO_DUE1-PadSDA1)") (class "Default")
      (node (ref "ARDUINO_DUE1") (pin "SDA1") (pinfunction "SDA1_SDA1") (pintype "bidirectional"))
    )
    (net (code "93") (name "unconnected-(ARDUINO_DUE1-PadVIN)") (class "Default")
      (node (ref "ARDUINO_DUE1") (pin "VIN") (pinfunction "VIN_VIN") (pintype "bidirectional"))
    )
    (net (code "94") (name "unconnected-(ARDUINO_DUE1-RX0<0-Pad0)") (class "Default")
      (node (ref "ARDUINO_DUE1") (pin "0") (pinfunction "RX0<0_0") (pintype "bidirectional"))
    )
    (net (code "95") (name "unconnected-(ARDUINO_DUE1-RX2_17-Pad17)") (class "Default")
      (node (ref "ARDUINO_DUE1") (pin "17") (pinfunction "RX2_17_17") (pintype "bidirectional"))
    )
    (net (code "96") (name "unconnected-(ARDUINO_DUE1-RX3_15-Pad15)") (class "Default")
      (node (ref "ARDUINO_DUE1") (pin "15") (pinfunction "RX3_15_15") (pintype "bidirectional"))
    )
    (net (code "97") (name "unconnected-(ARDUINO_DUE1-SCL_21-Pad21)") (class "Default")
      (node (ref "ARDUINO_DUE1") (pin "21") (pinfunction "SCL_21_21") (pintype "bidirectional"))
    )
    (net (code "98") (name "unconnected-(ARDUINO_DUE1-SDA_20-Pad20)") (class "Default")
      (node (ref "ARDUINO_DUE1") (pin "20") (pinfunction "SDA_20_20") (pintype "bidirectional"))
    )
    (net (code "99") (name "unconnected-(ARDUINO_DUE1-TX0>1-Pad1)") (class "Default")
      (node (ref "ARDUINO_DUE1") (pin "1") (pinfunction "TX0>1_1") (pintype "bidirectional"))
    )
    (net (code "100") (name "unconnected-(ARDUINO_DUE1-TX2_16-Pad16)") (class "Default")
      (node (ref "ARDUINO_DUE1") (pin "16") (pinfunction "TX2_16_16") (pintype "bidirectional"))
    )
    (net (code "101") (name "unconnected-(ARDUINO_DUE1-TX3_14-Pad14)") (class "Default")
      (node (ref "ARDUINO_DUE1") (pin "14") (pinfunction "TX3_14_14") (pintype "bidirectional"))
    )
    (net (code "102") (name "unconnected-(IC3E-O-Pad10)") (class "Default")
      (node (ref "IC3") (pin "10") (pinfunction "O_10") (pintype "output"))
    )
    (net (code "103") (name "unconnected-(IC3F-O-Pad12)") (class "Default")
      (node (ref "IC3") (pin "12") (pinfunction "O_12") (pintype "output"))
    )
  )
)
